# GE-PHY.net
KiCad netlist of a schematic drawn in Altium Designer
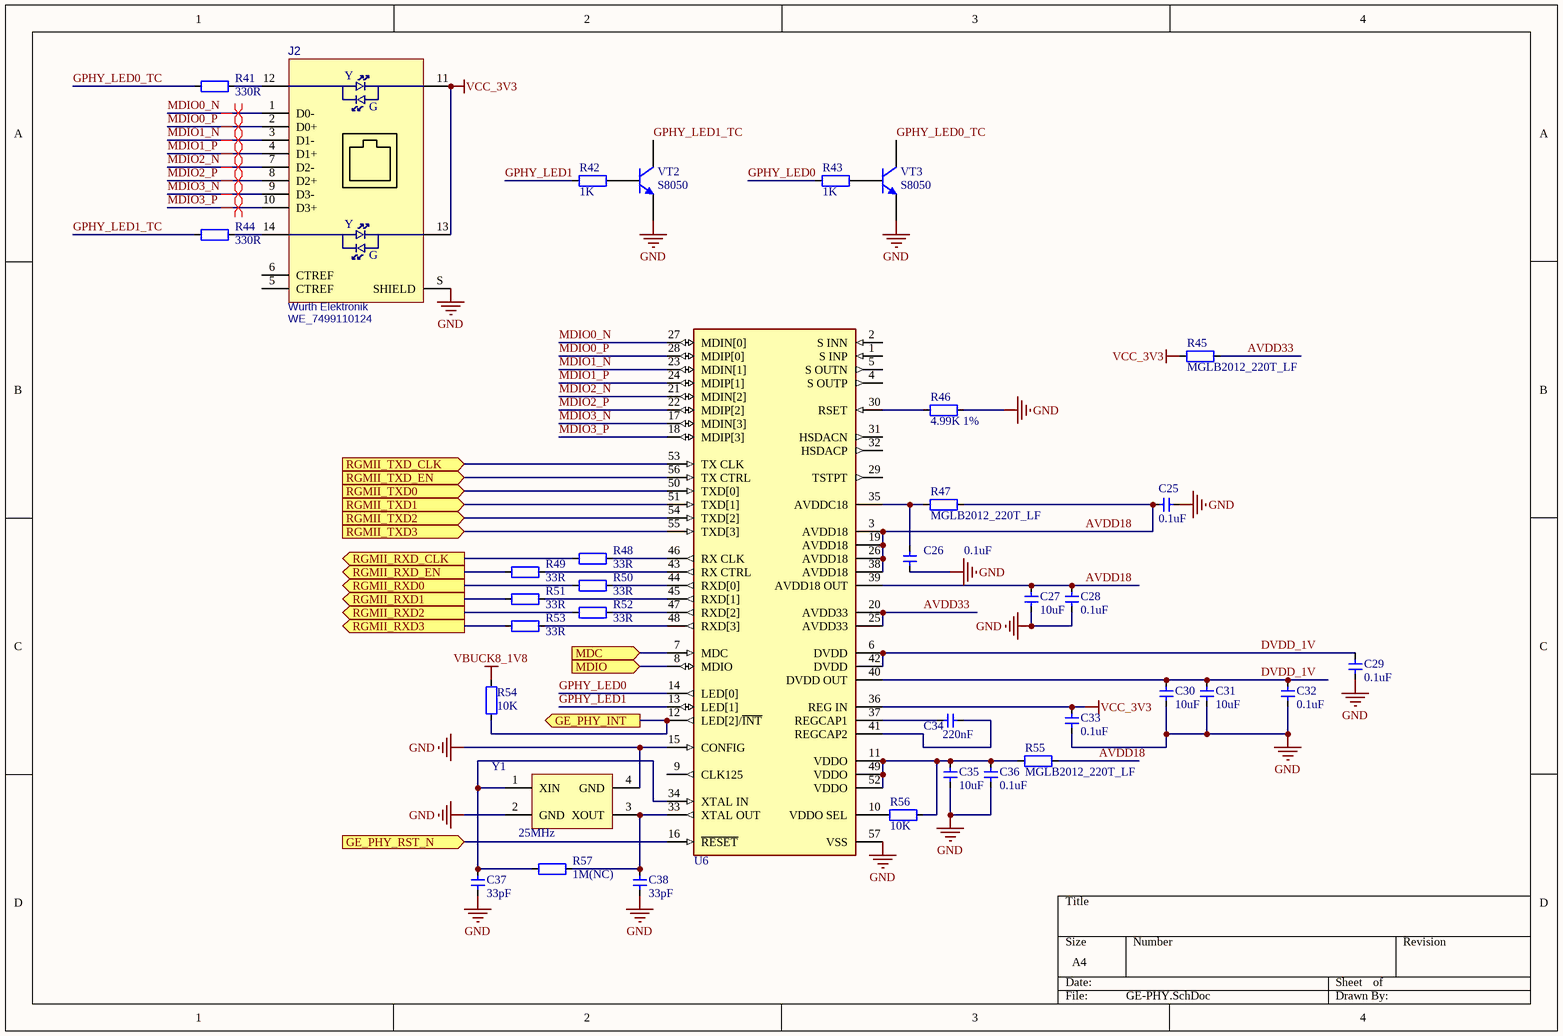
[diagram p0: GE-PHY.SchDoc]

(export (version "E")
  (design (tool "Eeschema 10.0.6"))
  (components
    (comp (ref "C25")
      (value "0.1uF")
      (footprint "CAP_0402")
      (description "Capacitor")
      (libsource (lib "MyPcbLib") (part "电容-0402"))
    )
    (comp (ref "C26")
      (value "0.1uF")
      (footprint "CAP_0402")
      (description "Capacitor")
      (libsource (lib "MyPcbLib") (part "电容-0402"))
    )
    (comp (ref "C27")
      (value "10uF")
      (footprint "CAP_0402")
      (description "Capacitor")
      (libsource (lib "MyPcbLib") (part "电容-0402"))
    )
    (comp (ref "C28")
      (value "0.1uF")
      (footprint "CAP_0402")
      (description "Capacitor")
      (libsource (lib "MyPcbLib") (part "电容-0402"))
    )
    (comp (ref "C29")
      (value "0.1uF")
      (footprint "CAP_0402")
      (description "Capacitor")
      (libsource (lib "MyPcbLib") (part "电容-0402"))
    )
    (comp (ref "C30")
      (value "10uF")
      (footprint "CAP_0402")
      (description "Capacitor")
      (libsource (lib "MyPcbLib") (part "电容-0402"))
    )
    (comp (ref "C31")
      (value "10uF")
      (footprint "CAP_0402")
      (description "Capacitor")
      (libsource (lib "MyPcbLib") (part "电容-0402"))
    )
    (comp (ref "C32")
      (value "0.1uF")
      (footprint "CAP_0402")
      (description "Capacitor")
      (libsource (lib "MyPcbLib") (part "电容-0402"))
    )
    (comp (ref "C33")
      (value "0.1uF")
      (footprint "CAP_0402")
      (description "Capacitor")
      (libsource (lib "MyPcbLib") (part "电容-0402"))
    )
    (comp (ref "C34")
      (value "220nF")
      (footprint "CAP_0402")
      (description "Capacitor")
      (libsource (lib "MyPcbLib") (part "电容-0402"))
    )
    (comp (ref "C35")
      (value "10uF")
      (footprint "CAP_0402")
      (description "Capacitor")
      (libsource (lib "MyPcbLib") (part "电容-0402"))
    )
    (comp (ref "C36")
      (value "0.1uF")
      (footprint "CAP_0402")
      (description "Capacitor")
      (libsource (lib "MyPcbLib") (part "电容-0402"))
    )
    (comp (ref "C37")
      (value "33pF")
      (footprint "CAP_0402")
      (description "Capacitor")
      (libsource (lib "MyPcbLib") (part "电容-0402"))
    )
    (comp (ref "C38")
      (value "33pF")
      (footprint "CAP_0402")
      (description "Capacitor")
      (libsource (lib "MyPcbLib") (part "电容-0402"))
    )
    (comp (ref "J2")
      (value "WE_7499110124")
      (footprint "GE-SOCKET")
      (description "LAN-Transformer WE-RJ45LAN 10/100/1000 BaseT")
      (fields (field (name "MANUFACTURER") "Wurth Elektronik") (field (name "PARTSYMBOL") "WE_7499110124"))
      (libsource (lib "MyPcbLib") (part "GE-SOCKET"))
    )
    (comp (ref "R41")
      (value "330R")
      (footprint "RES_0402")
      (description "Resistor")
      (libsource (lib "MyPcbLib") (part "电阻-0402"))
    )
    (comp (ref "R42")
      (value "1K")
      (footprint "RES_0402")
      (description "Resistor")
      (libsource (lib "") (part "电阻-0402_1"))
    )
    (comp (ref "R43")
      (value "1K")
      (footprint "RES_0402")
      (description "Resistor")
      (libsource (lib "") (part "电阻-0402_1"))
    )
    (comp (ref "R44")
      (value "330R")
      (footprint "RES_0402")
      (description "Resistor")
      (libsource (lib "MyPcbLib") (part "电阻-0402"))
    )
    (comp (ref "R45")
      (value "MGLB2012_220T_LF")
      (footprint "0805-L")
      (description "Resistor")
      (libsource (lib "MyPcbLib") (part "电阻-0805"))
    )
    (comp (ref "R46")
      (value "4.99K 1%")
      (footprint "RES_0402")
      (description "Resistor")
      (libsource (lib "") (part "电阻-0402_1"))
    )
    (comp (ref "R47")
      (value "MGLB2012_220T_LF")
      (footprint "0805-L")
      (description "Resistor")
      (libsource (lib "MyPcbLib") (part "电阻-0805"))
    )
    (comp (ref "R48")
      (value "33R")
      (footprint "RES_0402")
      (description "Resistor")
      (libsource (lib "MyPcbLib") (part "电阻-0402"))
    )
    (comp (ref "R49")
      (value "33R")
      (footprint "RES_0402")
      (description "Resistor")
      (libsource (lib "MyPcbLib") (part "电阻-0402"))
    )
    (comp (ref "R50")
      (value "33R")
      (footprint "RES_0402")
      (description "Resistor")
      (libsource (lib "MyPcbLib") (part "电阻-0402"))
    )
    (comp (ref "R51")
      (value "33R")
      (footprint "RES_0402")
      (description "Resistor")
      (libsource (lib "MyPcbLib") (part "电阻-0402"))
    )
    (comp (ref "R52")
      (value "33R")
      (footprint "RES_0402")
      (description "Resistor")
      (libsource (lib "MyPcbLib") (part "电阻-0402"))
    )
    (comp (ref "R53")
      (value "33R")
      (footprint "RES_0402")
      (description "Resistor")
      (libsource (lib "MyPcbLib") (part "电阻-0402"))
    )
    (comp (ref "R54")
      (value "10K")
      (footprint "RES_0402")
      (description "Resistor")
      (libsource (lib "") (part "电阻-0402_2"))
    )
    (comp (ref "R55")
      (value "MGLB2012_220T_LF")
      (footprint "0805-L")
      (description "Resistor")
      (libsource (lib "MyPcbLib") (part "电阻-0805"))
    )
    (comp (ref "R56")
      (value "10K")
      (footprint "RES_0402")
      (description "Resistor")
      (libsource (lib "") (part "电阻-0402_1"))
    )
    (comp (ref "R57")
      (value "1M(NC)")
      (footprint "RES_0402")
      (description "Resistor")
      (libsource (lib "MyPcbLib") (part "电阻-0402"))
    )
    (comp (ref "U6")
      (value "88E1512-A0-NNP2I000")
      (footprint "QFN-56")
      (libsource (lib "MyPcbLib") (part "88E1512-A0-NNP2I000"))
    )
    (comp (ref "VT2")
      (value "S8050")
      (footprint "SMT_TRIODE_NPN")
      (description "Surface mount NPN transistor, package SOT-23")
      (libsource (lib "MyPcbLib") (part "SMT_TRIODE_NPN"))
    )
    (comp (ref "VT3")
      (value "S8050")
      (footprint "SMT_TRIODE_NPN")
      (description "Surface mount NPN transistor, package SOT-23")
      (libsource (lib "MyPcbLib") (part "SMT_TRIODE_NPN"))
    )
    (comp (ref "Y1")
      (value "25MHz")
      (footprint "晶振2520")
      (description "2520无源")
      (fields (field (name "MF") "ECS International") (field (name "MP") "ECS-3225S30-240-EN-TR"))
      (libsource (lib "MyPcbLib") (part "晶振-4Pin-无源"))
    )
  )
  (nets
    (net (code "1") (name "/AVDD18") (class "Default")
      (node (ref "C25") (pin "1") (pinfunction "1_1") (pintype "passive"))
      (node (ref "C27") (pin "1") (pinfunction "1_1") (pintype "passive"))
      (node (ref "C28") (pin "1") (pinfunction "1_1") (pintype "passive"))
      (node (ref "R47") (pin "2") (pinfunction "2_2") (pintype "passive"))
      (node (ref "R55") (pin "2") (pinfunction "2_2") (pintype "passive"))
      (node (ref "U6") (pin "19") (pinfunction "AVDD18_19") (pintype "power_in"))
      (node (ref "U6") (pin "26") (pinfunction "AVDD18_26") (pintype "power_in"))
      (node (ref "U6") (pin "3") (pinfunction "AVDD18_3") (pintype "power_in"))
      (node (ref "U6") (pin "38") (pinfunction "AVDD18_38") (pintype "power_in"))
      (node (ref "U6") (pin "39") (pinfunction "AVDD18_OUT_39") (pintype "power_in"))
    )
    (net (code "2") (name "/AVDD33") (class "Default")
      (node (ref "R45") (pin "2") (pinfunction "2_2") (pintype "passive"))
      (node (ref "U6") (pin "20") (pinfunction "AVDD33_20") (pintype "power_in"))
      (node (ref "U6") (pin "25") (pinfunction "AVDD33_25") (pintype "power_in"))
    )
    (net (code "3") (name "/DVDD_1V") (class "Default")
      (node (ref "C29") (pin "1") (pinfunction "1_1") (pintype "passive"))
      (node (ref "C30") (pin "1") (pinfunction "1_1") (pintype "passive"))
      (node (ref "C31") (pin "1") (pinfunction "1_1") (pintype "passive"))
      (node (ref "C32") (pin "1") (pinfunction "1_1") (pintype "passive"))
      (node (ref "U6") (pin "40") (pinfunction "DVDD_OUT_40") (pintype "power_in"))
      (node (ref "U6") (pin "42") (pinfunction "DVDD_42") (pintype "power_in"))
      (node (ref "U6") (pin "6") (pinfunction "DVDD_6") (pintype "power_in"))
    )
    (net (code "4") (name "/GE_PHY_INT") (class "Default")
      (node (ref "R54") (pin "2") (pinfunction "2_2") (pintype "passive"))
      (node (ref "U6") (pin "12") (pinfunction "LED[2]/~{INT}_12") (pintype "output"))
    )
    (net (code "5") (name "/GE_PHY_RST_N") (class "Default")
      (node (ref "U6") (pin "16") (pinfunction "~{RESET}_16") (pintype "input"))
    )
    (net (code "6") (name "/GPHY_LED0") (class "Default")
      (node (ref "R43") (pin "1") (pinfunction "1_1") (pintype "passive"))
      (node (ref "U6") (pin "14") (pinfunction "LED[0]_14") (pintype "output"))
    )
    (net (code "7") (name "/GPHY_LED0_TC") (class "Default")
      (node (ref "R41") (pin "2") (pinfunction "2_2") (pintype "passive"))
      (node (ref "VT3") (pin "3") (pinfunction "C_3") (pintype "passive"))
    )
    (net (code "8") (name "/GPHY_LED1") (class "Default")
      (node (ref "R42") (pin "1") (pinfunction "1_1") (pintype "passive"))
      (node (ref "U6") (pin "13") (pinfunction "LED[1]_13") (pintype "bidirectional"))
    )
    (net (code "9") (name "/GPHY_LED1_TC") (class "Default")
      (node (ref "R44") (pin "2") (pinfunction "2_2") (pintype "passive"))
      (node (ref "VT2") (pin "3") (pinfunction "C_3") (pintype "passive"))
    )
    (net (code "10") (name "/MDC") (class "Default")
      (node (ref "U6") (pin "7") (pinfunction "MDC_7") (pintype "input"))
    )
    (net (code "11") (name "/MDIO") (class "Default")
      (node (ref "U6") (pin "8") (pinfunction "MDIO_8") (pintype "bidirectional"))
    )
    (net (code "12") (name "/MDIO0_N") (class "Default")
      (node (ref "J2") (pin "1") (pinfunction "D0-_1") (pintype "passive"))
      (node (ref "U6") (pin "27") (pinfunction "MDIN[0]_27") (pintype "bidirectional"))
    )
    (net (code "13") (name "/MDIO0_P") (class "Default")
      (node (ref "J2") (pin "2") (pinfunction "D0+_2") (pintype "passive"))
      (node (ref "U6") (pin "28") (pinfunction "MDIP[0]_28") (pintype "bidirectional"))
    )
    (net (code "14") (name "/MDIO1_N") (class "Default")
      (node (ref "J2") (pin "3") (pinfunction "D1-_3") (pintype "passive"))
      (node (ref "U6") (pin "23") (pinfunction "MDIN[1]_23") (pintype "bidirectional"))
    )
    (net (code "15") (name "/MDIO1_P") (class "Default")
      (node (ref "J2") (pin "4") (pinfunction "D1+_4") (pintype "passive"))
      (node (ref "U6") (pin "24") (pinfunction "MDIP[1]_24") (pintype "bidirectional"))
    )
    (net (code "16") (name "/MDIO2_N") (class "Default")
      (node (ref "J2") (pin "7") (pinfunction "D2-_7") (pintype "passive"))
      (node (ref "U6") (pin "21") (pinfunction "MDIN[2]_21") (pintype "bidirectional"))
    )
    (net (code "17") (name "/MDIO2_P") (class "Default")
      (node (ref "J2") (pin "8") (pinfunction "D2+_8") (pintype "passive"))
      (node (ref "U6") (pin "22") (pinfunction "MDIP[2]_22") (pintype "bidirectional"))
    )
    (net (code "18") (name "/MDIO3_N") (class "Default")
      (node (ref "J2") (pin "9") (pinfunction "D3-_9") (pintype "passive"))
      (node (ref "U6") (pin "17") (pinfunction "MDIN[3]_17") (pintype "bidirectional"))
    )
    (net (code "19") (name "/MDIO3_P") (class "Default")
      (node (ref "J2") (pin "10") (pinfunction "D3+_10") (pintype "passive"))
      (node (ref "U6") (pin "18") (pinfunction "MDIP[3]_18") (pintype "bidirectional"))
    )
    (net (code "20") (name "/RGMII_RXD0") (class "Default")
      (node (ref "R50") (pin "2") (pinfunction "2_2") (pintype "passive"))
    )
    (net (code "21") (name "/RGMII_RXD1") (class "Default")
      (node (ref "R51") (pin "2") (pinfunction "2_2") (pintype "passive"))
    )
    (net (code "22") (name "/RGMII_RXD2") (class "Default")
      (node (ref "R52") (pin "2") (pinfunction "2_2") (pintype "passive"))
    )
    (net (code "23") (name "/RGMII_RXD3") (class "Default")
      (node (ref "R53") (pin "2") (pinfunction "2_2") (pintype "passive"))
    )
    (net (code "24") (name "/RGMII_RXD_CLK") (class "Default")
      (node (ref "R48") (pin "2") (pinfunction "2_2") (pintype "passive"))
    )
    (net (code "25") (name "/RGMII_RXD_EN") (class "Default")
      (node (ref "R49") (pin "2") (pinfunction "2_2") (pintype "passive"))
    )
    (net (code "26") (name "/RGMII_TXD0") (class "Default")
      (node (ref "U6") (pin "50") (pinfunction "TXD[0]_50") (pintype "input"))
    )
    (net (code "27") (name "/RGMII_TXD1") (class "Default")
      (node (ref "U6") (pin "51") (pinfunction "TXD[1]_51") (pintype "input"))
    )
    (net (code "28") (name "/RGMII_TXD2") (class "Default")
      (node (ref "U6") (pin "54") (pinfunction "TXD[2]_54") (pintype "input"))
    )
    (net (code "29") (name "/RGMII_TXD3") (class "Default")
      (node (ref "U6") (pin "55") (pinfunction "TXD[3]_55") (pintype "input"))
    )
    (net (code "30") (name "/RGMII_TXD_CLK") (class "Default")
      (node (ref "U6") (pin "53") (pinfunction "TX_CLK_53") (pintype "input"))
    )
    (net (code "31") (name "/RGMII_TXD_EN") (class "Default")
      (node (ref "U6") (pin "56") (pinfunction "TX_CTRL_56") (pintype "input"))
    )
    (net (code "32") (name "GND") (class "Default")
      (node (ref "C25") (pin "2") (pinfunction "2_2") (pintype "passive"))
      (node (ref "C26") (pin "1") (pinfunction "1_1") (pintype "passive"))
      (node (ref "C27") (pin "2") (pinfunction "2_2") (pintype "passive"))
      (node (ref "C28") (pin "2") (pinfunction "2_2") (pintype "passive"))
      (node (ref "C29") (pin "2") (pinfunction "2_2") (pintype "passive"))
      (node (ref "C30") (pin "2") (pinfunction "2_2") (pintype "passive"))
      (node (ref "C31") (pin "2") (pinfunction "2_2") (pintype "passive"))
      (node (ref "C32") (pin "2") (pinfunction "2_2") (pintype "passive"))
      (node (ref "C33") (pin "2") (pinfunction "2_2") (pintype "passive"))
      (node (ref "C35") (pin "2") (pinfunction "2_2") (pintype "passive"))
      (node (ref "C36") (pin "2") (pinfunction "2_2") (pintype "passive"))
      (node (ref "C37") (pin "2") (pinfunction "2_2") (pintype "passive"))
      (node (ref "C38") (pin "2") (pinfunction "2_2") (pintype "passive"))
      (node (ref "J2") (pin "S") (pinfunction "SHIELD_S") (pintype "passive"))
      (node (ref "R46") (pin "2") (pinfunction "2_2") (pintype "passive"))
      (node (ref "U6") (pin "15") (pinfunction "CONFIG_15") (pintype "input"))
      (node (ref "U6") (pin "57") (pinfunction "VSS_57") (pintype "power_in"))
      (node (ref "VT2") (pin "2") (pinfunction "E_2") (pintype "passive"))
      (node (ref "VT3") (pin "2") (pinfunction "E_2") (pintype "passive"))
      (node (ref "Y1") (pin "2") (pinfunction "GND_2") (pintype "passive"))
      (node (ref "Y1") (pin "4") (pinfunction "GND_4") (pintype "passive"))
    )
    (net (code "33") (name "Net-(C35-Pad1)") (class "Default")
      (node (ref "C35") (pin "1") (pinfunction "1_1") (pintype "passive"))
      (node (ref "C36") (pin "1") (pinfunction "1_1") (pintype "passive"))
      (node (ref "R55") (pin "1") (pinfunction "1_1") (pintype "passive"))
      (node (ref "R56") (pin "2") (pinfunction "2_2") (pintype "passive"))
      (node (ref "U6") (pin "11") (pinfunction "VDDO_11") (pintype "power_in"))
      (node (ref "U6") (pin "49") (pinfunction "VDDO_49") (pintype "power_in"))
      (node (ref "U6") (pin "52") (pinfunction "VDDO_52") (pintype "power_in"))
    )
    (net (code "34") (name "Net-(J2-Pad12)") (class "Default")
      (node (ref "J2") (pin "12") (pinfunction "12_12") (pintype "passive"))
      (node (ref "R41") (pin "1") (pinfunction "1_1") (pintype "passive"))
    )
    (net (code "35") (name "Net-(J2-Pad14)") (class "Default")
      (node (ref "J2") (pin "14") (pinfunction "14_14") (pintype "passive"))
      (node (ref "R44") (pin "1") (pinfunction "1_1") (pintype "passive"))
    )
    (net (code "36") (name "Net-(U6-AVDDC18)") (class "Default")
      (node (ref "C26") (pin "2") (pinfunction "2_2") (pintype "passive"))
      (node (ref "R47") (pin "1") (pinfunction "1_1") (pintype "passive"))
      (node (ref "U6") (pin "35") (pinfunction "AVDDC18_35") (pintype "power_in"))
    )
    (net (code "37") (name "Net-(U6-REGCAP1)") (class "Default")
      (node (ref "C34") (pin "1") (pinfunction "1_1") (pintype "passive"))
      (node (ref "U6") (pin "37") (pinfunction "REGCAP1_37") (pintype "passive"))
    )
    (net (code "38") (name "Net-(U6-REGCAP2)") (class "Default")
      (node (ref "C34") (pin "2") (pinfunction "2_2") (pintype "passive"))
      (node (ref "U6") (pin "41") (pinfunction "REGCAP2_41") (pintype "passive"))
    )
    (net (code "39") (name "Net-(U6-RSET)") (class "Default")
      (node (ref "R46") (pin "1") (pinfunction "1_1") (pintype "passive"))
      (node (ref "U6") (pin "30") (pinfunction "RSET_30") (pintype "input"))
    )
    (net (code "40") (name "Net-(U6-RXD[0])") (class "Default")
      (node (ref "R50") (pin "1") (pinfunction "1_1") (pintype "passive"))
      (node (ref "U6") (pin "44") (pinfunction "RXD[0]_44") (pintype "output"))
    )
    (net (code "41") (name "Net-(U6-RXD[1])") (class "Default")
      (node (ref "R51") (pin "1") (pinfunction "1_1") (pintype "passive"))
      (node (ref "U6") (pin "45") (pinfunction "RXD[1]_45") (pintype "output"))
    )
    (net (code "42") (name "Net-(U6-RXD[2])") (class "Default")
      (node (ref "R52") (pin "1") (pinfunction "1_1") (pintype "passive"))
      (node (ref "U6") (pin "47") (pinfunction "RXD[2]_47") (pintype "output"))
    )
    (net (code "43") (name "Net-(U6-RXD[3])") (class "Default")
      (node (ref "R53") (pin "1") (pinfunction "1_1") (pintype "passive"))
      (node (ref "U6") (pin "48") (pinfunction "RXD[3]_48") (pintype "output"))
    )
    (net (code "44") (name "Net-(U6-RX_CLK)") (class "Default")
      (node (ref "R48") (pin "1") (pinfunction "1_1") (pintype "passive"))
      (node (ref "U6") (pin "46") (pinfunction "RX_CLK_46") (pintype "output"))
    )
    (net (code "45") (name "Net-(U6-RX_CTRL)") (class "Default")
      (node (ref "R49") (pin "1") (pinfunction "1_1") (pintype "passive"))
      (node (ref "U6") (pin "43") (pinfunction "RX_CTRL_43") (pintype "output"))
    )
    (net (code "46") (name "Net-(U6-VDDO_SEL)") (class "Default")
      (node (ref "R56") (pin "1") (pinfunction "1_1") (pintype "passive"))
      (node (ref "U6") (pin "10") (pinfunction "VDDO_SEL_10") (pintype "power_in"))
    )
    (net (code "47") (name "Net-(U6-XTAL_IN)") (class "Default")
      (node (ref "C37") (pin "1") (pinfunction "1_1") (pintype "passive"))
      (node (ref "R57") (pin "2") (pinfunction "2_2") (pintype "passive"))
      (node (ref "U6") (pin "34") (pinfunction "XTAL_IN_34") (pintype "input"))
      (node (ref "Y1") (pin "1") (pinfunction "XIN_1") (pintype "passive"))
    )
    (net (code "48") (name "Net-(U6-XTAL_OUT)") (class "Default")
      (node (ref "C38") (pin "1") (pinfunction "1_1") (pintype "passive"))
      (node (ref "R57") (pin "1") (pinfunction "1_1") (pintype "passive"))
      (node (ref "U6") (pin "33") (pinfunction "XTAL_OUT_33") (pintype "output"))
      (node (ref "Y1") (pin "3") (pinfunction "XOUT_3") (pintype "passive"))
    )
    (net (code "49") (name "Net-(VT2-B)") (class "Default")
      (node (ref "R42") (pin "2") (pinfunction "2_2") (pintype "passive"))
      (node (ref "VT2") (pin "1") (pinfunction "B_1") (pintype "passive"))
    )
    (net (code "50") (name "Net-(VT3-B)") (class "Default")
      (node (ref "R43") (pin "2") (pinfunction "2_2") (pintype "passive"))
      (node (ref "VT3") (pin "1") (pinfunction "B_1") (pintype "passive"))
    )
    (net (code "51") (name "VBUCK8_1V8") (class "Default")
      (node (ref "R54") (pin "1") (pinfunction "1_1") (pintype "passive"))
    )
    (net (code "52") (name "VCC_3V3") (class "Default")
      (node (ref "C33") (pin "1") (pinfunction "1_1") (pintype "passive"))
      (node (ref "J2") (pin "11") (pinfunction "11_11") (pintype "passive"))
      (node (ref "J2") (pin "13") (pinfunction "13_13") (pintype "passive"))
      (node (ref "R45") (pin "1") (pinfunction "1_1") (pintype "passive"))
      (node (ref "U6") (pin "36") (pinfunction "REG_IN_36") (pintype "power_in"))
    )
    (net (code "53") (name "unconnected-(J2-CTREF-Pad5)") (class "Default")
      (node (ref "J2") (pin "5") (pinfunction "CTREF_5") (pintype "passive"))
    )
    (net (code "54") (name "unconnected-(J2-CTREF-Pad6)") (class "Default")
      (node (ref "J2") (pin "6") (pinfunction "CTREF_6") (pintype "passive"))
    )
    (net (code "55") (name "unconnected-(U6-CLK125-Pad9)") (class "Default")
      (node (ref "U6") (pin "9") (pinfunction "CLK125_9") (pintype "output"))
    )
    (net (code "56") (name "unconnected-(U6-HSDACN-Pad31)") (class "Default")
      (node (ref "U6") (pin "31") (pinfunction "HSDACN_31") (pintype "output"))
    )
    (net (code "57") (name "unconnected-(U6-HSDACP-Pad32)") (class "Default")
      (node (ref "U6") (pin "32") (pinfunction "HSDACP_32") (pintype "output"))
    )
    (net (code "58") (name "unconnected-(U6-S_INN-Pad2)") (class "Default")
      (node (ref "U6") (pin "2") (pinfunction "S_INN_2") (pintype "input"))
    )
    (net (code "59") (name "unconnected-(U6-S_INP-Pad1)") (class "Default")
      (node (ref "U6") (pin "1") (pinfunction "S_INP_1") (pintype "input"))
    )
    (net (code "60") (name "unconnected-(U6-S_OUTN-Pad5)") (class "Default")
      (node (ref "U6") (pin "5") (pinfunction "S_OUTN_5") (pintype "output"))
    )
    (net (code "61") (name "unconnected-(U6-S_OUTP-Pad4)") (class "Default")
      (node (ref "U6") (pin "4") (pinfunction "S_OUTP_4") (pintype "output"))
    )
    (net (code "62") (name "unconnected-(U6-TSTPT-Pad29)") (class "Default")
      (node (ref "U6") (pin "29") (pinfunction "TSTPT_29") (pintype "output"))
    )
  )
)
